# Fonte.net
KiCad netlist of a schematic drawn in EAGLE
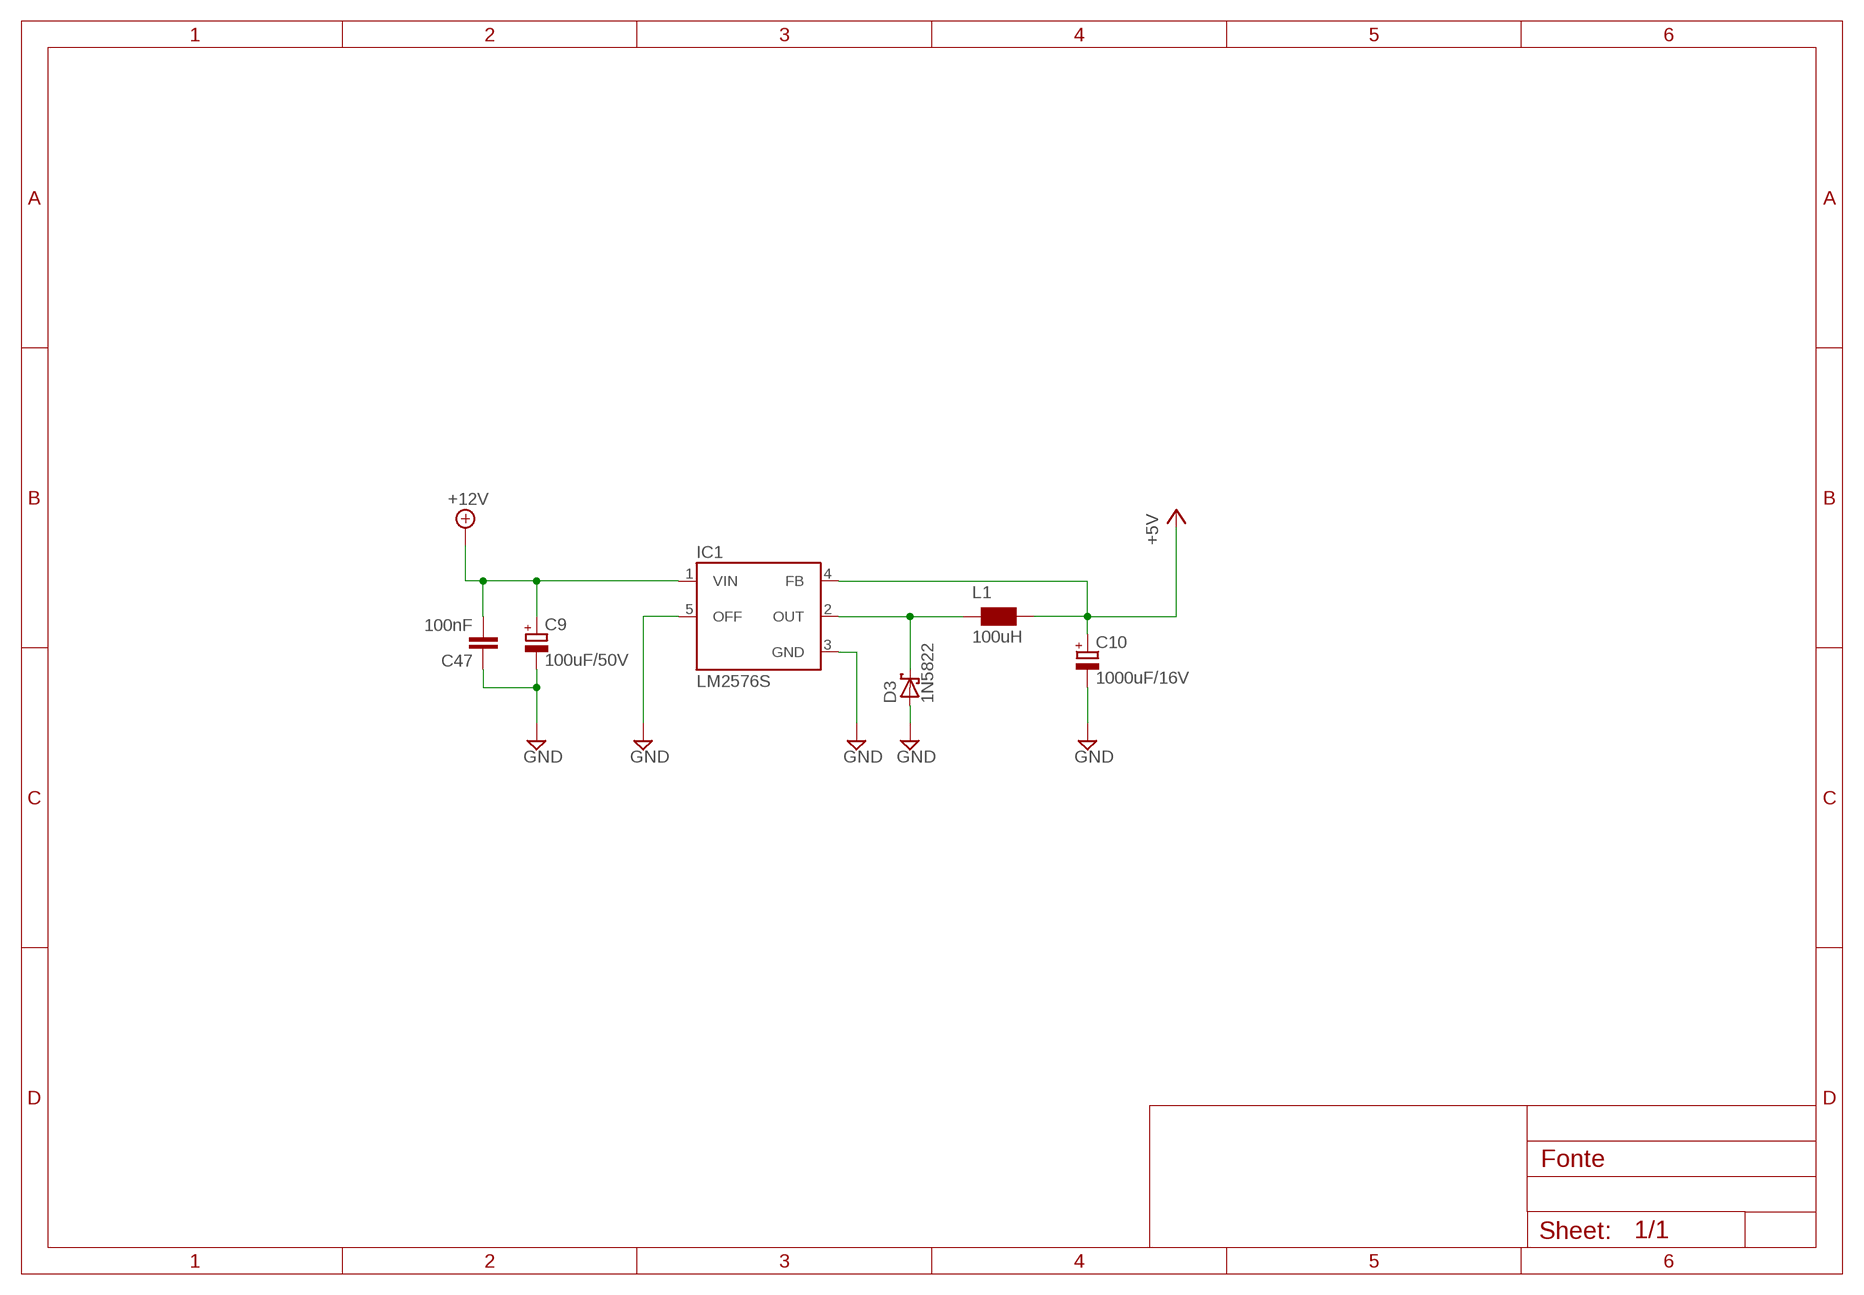
[diagram p0: schematic, sheet 1]

(export (version "E")
  (design (tool "Eeschema 10.0.6"))
  (components
    (comp (ref "C9")
      (value "100uF/50V")
      (footprint "eagle-import:E3,5-8")
      (libsource (lib "eagle-import") (part "CPOL-EUE3.5-8"))
    )
    (comp (ref "C10")
      (value "1000uF/16V")
      (footprint "eagle-import:E5-10,5")
      (libsource (lib "eagle-import") (part "CPOL-EUE5-10.5"))
    )
    (comp (ref "C47")
      (value "100nF")
      (footprint "eagle-import:C0805")
      (libsource (lib "eagle-import") (part "C-EUC0805"))
    )
    (comp (ref "D3")
      (value "1N5822")
      (footprint "eagle-import:DO201T15")
      (libsource (lib "eagle-import") (part "SCHOTTKY-DIODEDO201T15"))
    )
    (comp (ref "IC1")
      (value "LM2576S")
      (footprint "eagle-import:TO263-5")
      (libsource (lib "eagle-import") (part "LM2576S"))
    )
    (comp (ref "L1")
      (value "100uH")
      (footprint "eagle-import:L")
      (libsource (lib "eagle-import") (part "WE-PD4_L"))
    )
  )
  (nets
    (net (code "1") (name "+5V") (class "Default")
      (node (ref "C10") (pin "+") (pinfunction "+_+") (pintype "passive"))
      (node (ref "IC1") (pin "4") (pinfunction "FB_4") (pintype "input"))
      (node (ref "L1") (pin "1") (pinfunction "2_1") (pintype "passive"))
    )
    (net (code "2") (name "+12V") (class "Default")
      (node (ref "C47") (pin "2") (pinfunction "2_2") (pintype "passive"))
      (node (ref "C9") (pin "+") (pinfunction "+_+") (pintype "passive"))
      (node (ref "IC1") (pin "1") (pinfunction "VIN_1") (pintype "power_in"))
    )
    (net (code "3") (name "GND") (class "Default")
      (node (ref "C10") (pin "-") (pinfunction "-_-") (pintype "passive"))
      (node (ref "C47") (pin "1") (pinfunction "1_1") (pintype "passive"))
      (node (ref "C9") (pin "-") (pinfunction "-_-") (pintype "passive"))
      (node (ref "D3") (pin "A") (pinfunction "A_A") (pintype "passive"))
      (node (ref "IC1") (pin "3") (pinfunction "GND_3") (pintype "power_in"))
      (node (ref "IC1") (pin "5") (pinfunction "OFF_5") (pintype "input"))
    )
    (net (code "4") (name "Net-(IC1-OUT)") (class "Default")
      (node (ref "D3") (pin "C") (pinfunction "C_C") (pintype "passive"))
      (node (ref "IC1") (pin "2") (pinfunction "OUT_2") (pintype "output"))
      (node (ref "L1") (pin "2") (pinfunction "1_2") (pintype "passive"))
    )
  )
)
